# Xmega.net
KiCad netlist of a schematic drawn in Altium Designer
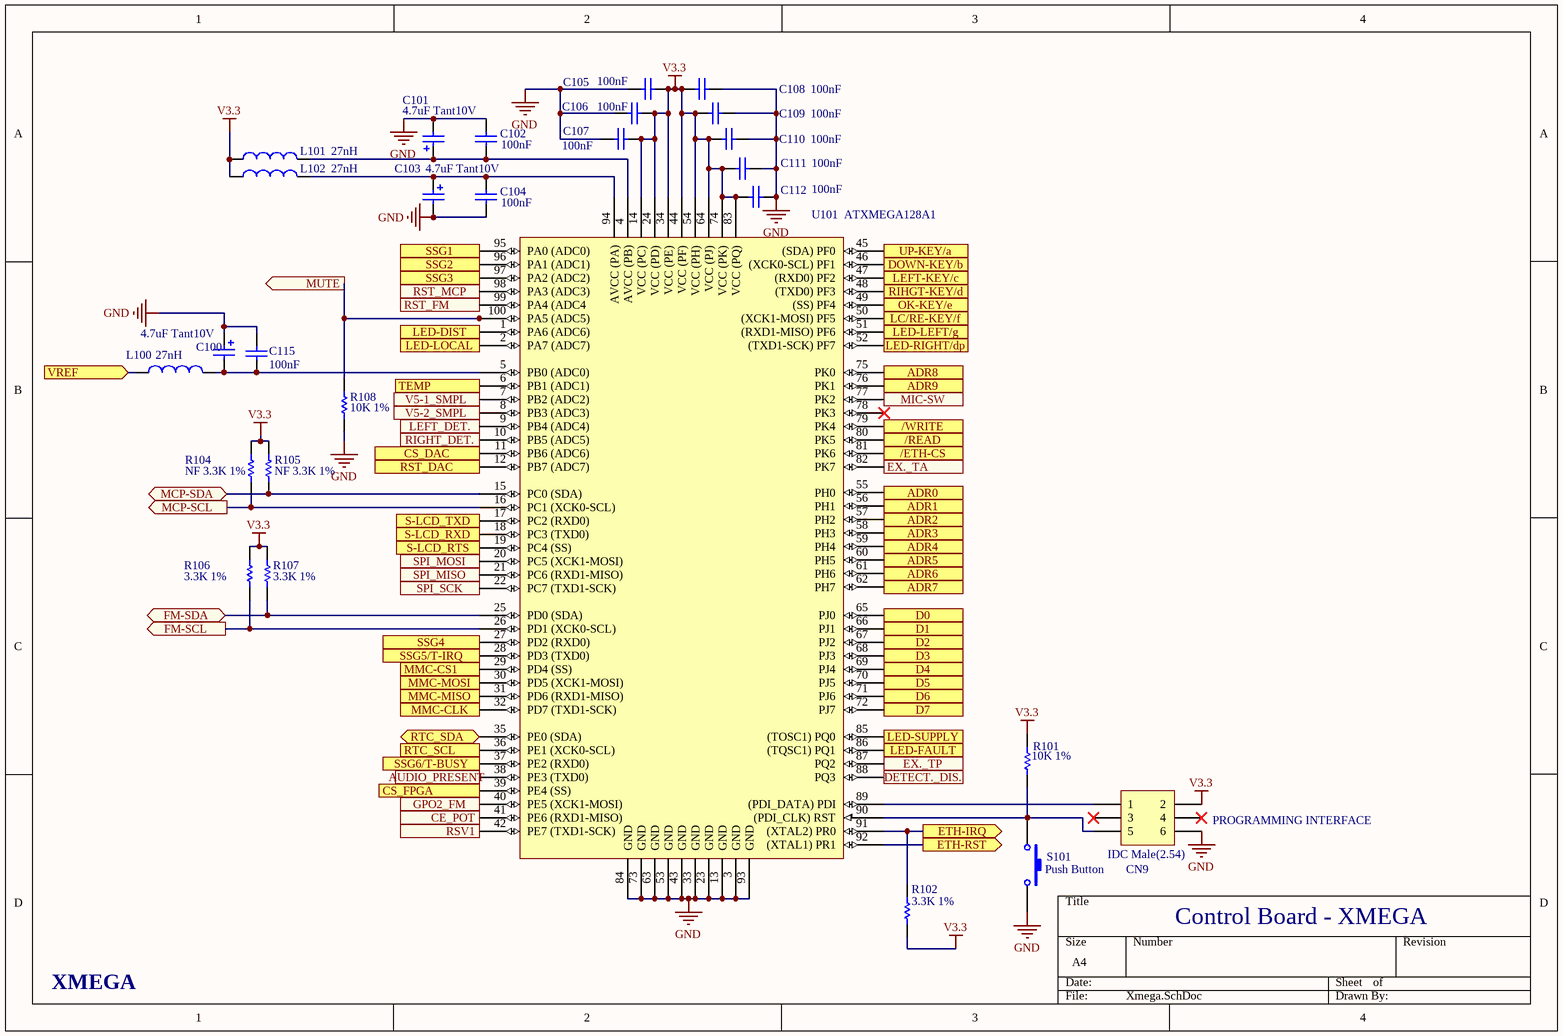
[diagram p0: Xmega.SchDoc]

(export (version "E")
  (design (tool "Eeschema 10.0.6"))
  (components
    (comp (ref "C100")
      (value "4.7uF Tant10V")
      (footprint "CAP-TAN")
      (description "Polarized Capacitor (Surface Mount)")
      (fields (field (name "PUBLISHER") "Altium Limited"))
      (libsource (lib "Miscellaneous Devices") (part "Cap Pol3"))
    )
    (comp (ref "C101")
      (value "4.7uF Tant10V")
      (footprint "A")
      (description "Polarized Capacitor (Surface Mount)")
      (fields (field (name "PUBLISHER") "Altium Limited"))
      (libsource (lib "Miscellaneous Devices") (part "Cap Pol3"))
    )
    (comp (ref "C102")
      (value "100nF")
      (footprint "1206_FA")
      (description "Capacitor (Semiconductor SIM Model)")
      (fields (field (name "PUBLISHER") "Altium Limited"))
      (libsource (lib "Miscellaneous Devices") (part "Cap Semi"))
    )
    (comp (ref "C103")
      (value "4.7uF Tant10V")
      (footprint "A")
      (description "Polarized Capacitor (Surface Mount)")
      (fields (field (name "PUBLISHER") "Altium Limited"))
      (libsource (lib "Miscellaneous Devices") (part "Cap Pol3"))
    )
    (comp (ref "C104")
      (value "100nF")
      (footprint "1206_FA")
      (description "Capacitor (Semiconductor SIM Model)")
      (fields (field (name "PUBLISHER") "Altium Limited"))
      (libsource (lib "Miscellaneous Devices") (part "Cap Semi"))
    )
    (comp (ref "C105")
      (value "100nF")
      (footprint "1206_FA")
      (description "Capacitor (Semiconductor SIM Model)")
      (fields (field (name "PUBLISHER") "Altium Limited"))
      (libsource (lib "Miscellaneous Devices") (part "Cap Semi"))
    )
    (comp (ref "C106")
      (value "100nF")
      (footprint "1206_FA")
      (description "Capacitor (Semiconductor SIM Model)")
      (fields (field (name "PUBLISHER") "Altium Limited"))
      (libsource (lib "Miscellaneous Devices") (part "Cap Semi"))
    )
    (comp (ref "C107")
      (value "100nF")
      (footprint "1206_FA")
      (description "Capacitor (Semiconductor SIM Model)")
      (fields (field (name "PUBLISHER") "Altium Limited"))
      (libsource (lib "Miscellaneous Devices") (part "Cap Semi"))
    )
    (comp (ref "C108")
      (value "100nF")
      (footprint "1206_FA")
      (description "Capacitor (Semiconductor SIM Model)")
      (fields (field (name "PUBLISHER") "Altium Limited"))
      (libsource (lib "Miscellaneous Devices") (part "Cap Semi"))
    )
    (comp (ref "C109")
      (value "100nF")
      (footprint "1206_FA")
      (description "Capacitor (Semiconductor SIM Model)")
      (fields (field (name "PUBLISHER") "Altium Limited"))
      (libsource (lib "Miscellaneous Devices") (part "Cap Semi"))
    )
    (comp (ref "C110")
      (value "100nF")
      (footprint "1206_FA")
      (description "Capacitor (Semiconductor SIM Model)")
      (fields (field (name "PUBLISHER") "Altium Limited"))
      (libsource (lib "Miscellaneous Devices") (part "Cap Semi"))
    )
    (comp (ref "C111")
      (value "100nF")
      (footprint "1206_FA")
      (description "Capacitor (Semiconductor SIM Model)")
      (fields (field (name "PUBLISHER") "Altium Limited"))
      (libsource (lib "Miscellaneous Devices") (part "Cap Semi"))
    )
    (comp (ref "C112")
      (value "100nF")
      (footprint "1206_FA")
      (description "Capacitor (Semiconductor SIM Model)")
      (fields (field (name "PUBLISHER") "Altium Limited"))
      (libsource (lib "Miscellaneous Devices") (part "Cap Semi"))
    )
    (comp (ref "C115")
      (value "100nF")
      (footprint "0805_FA")
      (description "Capacitor (Semiconductor SIM Model)")
      (fields (field (name "PUBLISHER") "Altium Limited"))
      (libsource (lib "Miscellaneous Devices") (part "Cap Semi"))
    )
    (comp (ref "CN9")
      (value "IDC Male(2.54)")
      (footprint "HDR2X3_M")
      (description "Header 3x2")
      (fields (field (name "PUBLISHER") "Altium Limited"))
      (libsource (lib "Miscellaneous Connectors") (part "Header 3X2"))
    )
    (comp (ref "L100")
      (value "27nH")
      (footprint "1210_FA")
      (description "Inductor")
      (fields (field (name "PUBLISHER") "Altium Limited"))
      (libsource (lib "Miscellaneous Devices") (part "Inductor"))
    )
    (comp (ref "L101")
      (value "27nH")
      (footprint "1210_FA")
      (description "Inductor")
      (fields (field (name "PUBLISHER") "Altium Limited"))
      (libsource (lib "Miscellaneous Devices") (part "Inductor"))
    )
    (comp (ref "L102")
      (value "27nH")
      (footprint "1210_FA")
      (description "Inductor")
      (fields (field (name "PUBLISHER") "Altium Limited"))
      (libsource (lib "Miscellaneous Devices") (part "Inductor"))
    )
    (comp (ref "R101")
      (value "10K 1%")
      (footprint "1206_FA")
      (description "Semiconductor Resistor")
      (fields (field (name "PUBLISHER") "Altium Limited"))
      (libsource (lib "Miscellaneous Devices") (part "Res Semi"))
    )
    (comp (ref "R102")
      (value "3.3K 1%")
      (footprint "1206_FA")
      (description "Semiconductor Resistor")
      (fields (field (name "PUBLISHER") "Altium Limited"))
      (libsource (lib "Miscellaneous Devices") (part "Res Semi"))
    )
    (comp (ref "R104")
      (value "NF 3.3K 1%")
      (footprint "1206_FA")
      (description "Semiconductor Resistor")
      (fields (field (name "PUBLISHER") "Altium Limited"))
      (libsource (lib "Miscellaneous Devices") (part "Res Semi"))
    )
    (comp (ref "R105")
      (value "NF 3.3K 1%")
      (footprint "1206_FA")
      (description "Semiconductor Resistor")
      (fields (field (name "PUBLISHER") "Altium Limited"))
      (libsource (lib "Miscellaneous Devices") (part "Res Semi"))
    )
    (comp (ref "R106")
      (value "3.3K 1%")
      (footprint "1206_FA")
      (description "Semiconductor Resistor")
      (fields (field (name "PUBLISHER") "Altium Limited"))
      (libsource (lib "Miscellaneous Devices") (part "Res Semi"))
    )
    (comp (ref "R107")
      (value "3.3K 1%")
      (footprint "1206_FA")
      (description "Semiconductor Resistor")
      (fields (field (name "PUBLISHER") "Altium Limited"))
      (libsource (lib "Miscellaneous Devices") (part "Res Semi"))
    )
    (comp (ref "R108")
      (value "10K 1%")
      (footprint "1206_FA")
      (description "Semiconductor Resistor")
      (fields (field (name "PUBLISHER") "Altium Limited"))
      (libsource (lib "Miscellaneous Devices") (part "Res Semi"))
    )
    (comp (ref "S101")
      (value "Push Button")
      (footprint "SPS2_M(2Pin)")
      (description "Switch")
      (fields (field (name "PUBLISHER") "Altium Limited"))
      (libsource (lib "Miscellaneous Devices") (part "SW-PB"))
    )
    (comp (ref "U101")
      (value "ATXMEGA128A1")
      (footprint "100T1_N")
      (description "Atmel Microcontroller - Library created by carel..  <www.mpfreezone.com>")
      (libsource (lib "Xmega") (part "ATMEGA163_DIP40"))
    )
  )
  (nets
    (net (code "1") (name "/ADR0") (class "Default")
      (node (ref "U101") (pin "55") (pinfunction "PH0_55") (pintype "bidirectional"))
    )
    (net (code "2") (name "/ADR1") (class "Default")
      (node (ref "U101") (pin "56") (pinfunction "PH1_56") (pintype "bidirectional"))
    )
    (net (code "3") (name "/ADR2") (class "Default")
      (node (ref "U101") (pin "57") (pinfunction "PH2_57") (pintype "bidirectional"))
    )
    (net (code "4") (name "/ADR3") (class "Default")
      (node (ref "U101") (pin "58") (pinfunction "PH3_58") (pintype "bidirectional"))
    )
    (net (code "5") (name "/ADR4") (class "Default")
      (node (ref "U101") (pin "59") (pinfunction "PH4_59") (pintype "bidirectional"))
    )
    (net (code "6") (name "/ADR5") (class "Default")
      (node (ref "U101") (pin "60") (pinfunction "PH5_60") (pintype "bidirectional"))
    )
    (net (code "7") (name "/ADR6") (class "Default")
      (node (ref "U101") (pin "61") (pinfunction "PH6_61") (pintype "bidirectional"))
    )
    (net (code "8") (name "/ADR7") (class "Default")
      (node (ref "U101") (pin "62") (pinfunction "PH7_62") (pintype "bidirectional"))
    )
    (net (code "9") (name "/ADR8") (class "Default")
      (node (ref "U101") (pin "75") (pinfunction "PK0_75") (pintype "bidirectional"))
    )
    (net (code "10") (name "/ADR9") (class "Default")
      (node (ref "U101") (pin "76") (pinfunction "PK1_76") (pintype "bidirectional"))
    )
    (net (code "11") (name "/AUDIO_PRESENT") (class "Default")
      (node (ref "U101") (pin "38") (pinfunction "PE3_(TXD0)_38") (pintype "bidirectional"))
    )
    (net (code "12") (name "/CE_POT") (class "Default")
      (node (ref "U101") (pin "41") (pinfunction "PE6_(RXD1-MISO)_41") (pintype "bidirectional"))
    )
    (net (code "13") (name "/CS_DAC") (class "Default")
      (node (ref "U101") (pin "11") (pinfunction "PB6_(ADC6)_11") (pintype "bidirectional"))
    )
    (net (code "14") (name "/CS_FPGA") (class "Default")
      (node (ref "U101") (pin "39") (pinfunction "PE4_(SS)_39") (pintype "bidirectional"))
    )
    (net (code "15") (name "/D0") (class "Default")
      (node (ref "U101") (pin "65") (pinfunction "PJ0_65") (pintype "bidirectional"))
    )
    (net (code "16") (name "/D1") (class "Default")
      (node (ref "U101") (pin "66") (pinfunction "PJ1_66") (pintype "bidirectional"))
    )
    (net (code "17") (name "/D2") (class "Default")
      (node (ref "U101") (pin "67") (pinfunction "PJ2_67") (pintype "bidirectional"))
    )
    (net (code "18") (name "/D3") (class "Default")
      (node (ref "U101") (pin "68") (pinfunction "PJ3_68") (pintype "bidirectional"))
    )
    (net (code "19") (name "/D4") (class "Default")
      (node (ref "U101") (pin "69") (pinfunction "PJ4_69") (pintype "bidirectional"))
    )
    (net (code "20") (name "/D5") (class "Default")
      (node (ref "U101") (pin "70") (pinfunction "PJ5_70") (pintype "bidirectional"))
    )
    (net (code "21") (name "/D6") (class "Default")
      (node (ref "U101") (pin "71") (pinfunction "PJ6_71") (pintype "bidirectional"))
    )
    (net (code "22") (name "/D7") (class "Default")
      (node (ref "U101") (pin "72") (pinfunction "PJ7_72") (pintype "bidirectional"))
    )
    (net (code "23") (name "/DETECT._DIS.") (class "Default")
      (node (ref "U101") (pin "88") (pinfunction "PQ3_88") (pintype "bidirectional"))
    )
    (net (code "24") (name "/DOWN-KEY{slash}b") (class "Default")
      (node (ref "U101") (pin "46") (pinfunction "(XCK0-SCL)_PF1_46") (pintype "bidirectional"))
    )
    (net (code "25") (name "/ETH-IRQ") (class "Default")
      (node (ref "R102") (pin "2") (pinfunction "2_2") (pintype "passive"))
      (node (ref "U101") (pin "91") (pinfunction "(XTAL2)_PR0_91") (pintype "bidirectional"))
    )
    (net (code "26") (name "/ETH-RST") (class "Default")
      (node (ref "U101") (pin "92") (pinfunction "(XTAL1)_PR1_92") (pintype "bidirectional"))
    )
    (net (code "27") (name "/EX._TA") (class "Default")
      (node (ref "U101") (pin "82") (pinfunction "PK7_82") (pintype "bidirectional"))
    )
    (net (code "28") (name "/EX._TP") (class "Default")
      (node (ref "U101") (pin "87") (pinfunction "PQ2_87") (pintype "bidirectional"))
    )
    (net (code "29") (name "/FM-SCL") (class "Default")
      (node (ref "R106") (pin "1") (pinfunction "1_1") (pintype "passive"))
      (node (ref "U101") (pin "26") (pinfunction "PD1_(XCK0-SCL)_26") (pintype "bidirectional"))
    )
    (net (code "30") (name "/FM-SDA") (class "Default")
      (node (ref "R107") (pin "1") (pinfunction "1_1") (pintype "passive"))
      (node (ref "U101") (pin "25") (pinfunction "PD0_(SDA)_25") (pintype "bidirectional"))
    )
    (net (code "31") (name "/GPO2_FM") (class "Default")
      (node (ref "U101") (pin "40") (pinfunction "PE5_(XCK1-MOSI)_40") (pintype "bidirectional"))
    )
    (net (code "32") (name "/LC{slash}RE-KEY{slash}f") (class "Default")
      (node (ref "U101") (pin "50") (pinfunction "(XCK1-MOSI)_PF5_50") (pintype "bidirectional"))
    )
    (net (code "33") (name "/LED-DIST") (class "Default")
      (node (ref "U101") (pin "1") (pinfunction "PA6_(ADC6)_1") (pintype "bidirectional"))
    )
    (net (code "34") (name "/LED-FAULT") (class "Default")
      (node (ref "U101") (pin "86") (pinfunction "(TQSC1)_PQ1_86") (pintype "bidirectional"))
    )
    (net (code "35") (name "/LED-LEFT{slash}g") (class "Default")
      (node (ref "U101") (pin "51") (pinfunction "(RXD1-MISO)_PF6_51") (pintype "bidirectional"))
    )
    (net (code "36") (name "/LED-LOCAL") (class "Default")
      (node (ref "U101") (pin "2") (pinfunction "PA7_(ADC7)_2") (pintype "bidirectional"))
    )
    (net (code "37") (name "/LED-RIGHT{slash}dp") (class "Default")
      (node (ref "U101") (pin "52") (pinfunction "(TXD1-SCK)_PF7_52") (pintype "bidirectional"))
    )
    (net (code "38") (name "/LED-SUPPLY") (class "Default")
      (node (ref "U101") (pin "85") (pinfunction "(TOSC1)_PQ0_85") (pintype "bidirectional"))
    )
    (net (code "39") (name "/LEFT-KEY{slash}c") (class "Default")
      (node (ref "U101") (pin "47") (pinfunction "(RXD0)_PF2_47") (pintype "bidirectional"))
    )
    (net (code "40") (name "/LEFT_DET.") (class "Default")
      (node (ref "U101") (pin "9") (pinfunction "PB4_(ADC4)_9") (pintype "bidirectional"))
    )
    (net (code "41") (name "/MCP-SCL") (class "Default")
      (node (ref "R104") (pin "1") (pinfunction "1_1") (pintype "passive"))
      (node (ref "U101") (pin "16") (pinfunction "PC1_(XCK0-SCL)_16") (pintype "bidirectional"))
    )
    (net (code "42") (name "/MCP-SDA") (class "Default")
      (node (ref "R105") (pin "1") (pinfunction "1_1") (pintype "passive"))
      (node (ref "U101") (pin "15") (pinfunction "PC0_(SDA)_15") (pintype "bidirectional"))
    )
    (net (code "43") (name "/MIC-SW") (class "Default")
      (node (ref "U101") (pin "77") (pinfunction "PK2_77") (pintype "bidirectional"))
    )
    (net (code "44") (name "/MMC-CLK") (class "Default")
      (node (ref "U101") (pin "32") (pinfunction "PD7_(TXD1-SCK)_32") (pintype "bidirectional"))
    )
    (net (code "45") (name "/MMC-CS1") (class "Default")
      (node (ref "U101") (pin "29") (pinfunction "PD4_(SS)_29") (pintype "bidirectional"))
    )
    (net (code "46") (name "/MMC-MISO") (class "Default")
      (node (ref "U101") (pin "31") (pinfunction "PD6_(RXD1-MISO)_31") (pintype "bidirectional"))
    )
    (net (code "47") (name "/MMC-MOSI") (class "Default")
      (node (ref "U101") (pin "30") (pinfunction "PD5_(XCK1-MOSI)_30") (pintype "bidirectional"))
    )
    (net (code "48") (name "/MUTE") (class "Default")
      (node (ref "R108") (pin "2") (pinfunction "2_2") (pintype "passive"))
      (node (ref "U101") (pin "100") (pinfunction "PA5_(ADC5)_100") (pintype "bidirectional"))
    )
    (net (code "49") (name "/OK-KEY{slash}e") (class "Default")
      (node (ref "U101") (pin "49") (pinfunction "(SS)_PF4_49") (pintype "bidirectional"))
    )
    (net (code "50") (name "/RIGHT_DET.") (class "Default")
      (node (ref "U101") (pin "10") (pinfunction "PB5_(ADC5)_10") (pintype "bidirectional"))
    )
    (net (code "51") (name "/RIHGT-KEY{slash}d") (class "Default")
      (node (ref "U101") (pin "48") (pinfunction "(TXD0)_PF3_48") (pintype "bidirectional"))
    )
    (net (code "52") (name "/RST_DAC") (class "Default")
      (node (ref "U101") (pin "12") (pinfunction "PB7_(ADC7)_12") (pintype "bidirectional"))
    )
    (net (code "53") (name "/RST_FM") (class "Default")
      (node (ref "U101") (pin "99") (pinfunction "PA4_(ADC4_99") (pintype "bidirectional"))
    )
    (net (code "54") (name "/RST_MCP") (class "Default")
      (node (ref "U101") (pin "98") (pinfunction "PA3_(ADC3)_98") (pintype "bidirectional"))
    )
    (net (code "55") (name "/RSV1") (class "Default")
      (node (ref "U101") (pin "42") (pinfunction "PE7_(TXD1-SCK)_42") (pintype "bidirectional"))
    )
    (net (code "56") (name "/RTC_SCL") (class "Default")
      (node (ref "U101") (pin "36") (pinfunction "PE1_(XCK0-SCL)_36") (pintype "bidirectional"))
    )
    (net (code "57") (name "/RTC_SDA") (class "Default")
      (node (ref "U101") (pin "35") (pinfunction "PE0_(SDA)_35") (pintype "bidirectional"))
    )
    (net (code "58") (name "/S-LCD_RTS") (class "Default")
      (node (ref "U101") (pin "19") (pinfunction "PC4_(SS)_19") (pintype "bidirectional"))
    )
    (net (code "59") (name "/S-LCD_RXD") (class "Default")
      (node (ref "U101") (pin "18") (pinfunction "PC3_(TXD0)_18") (pintype "bidirectional"))
    )
    (net (code "60") (name "/S-LCD_TXD") (class "Default")
      (node (ref "U101") (pin "17") (pinfunction "PC2_(RXD0)_17") (pintype "bidirectional"))
    )
    (net (code "61") (name "/SPI_MISO") (class "Default")
      (node (ref "U101") (pin "21") (pinfunction "PC6_(RXD1-MISO)_21") (pintype "bidirectional"))
    )
    (net (code "62") (name "/SPI_MOSI") (class "Default")
      (node (ref "U101") (pin "20") (pinfunction "PC5_(XCK1-MOSI)_20") (pintype "bidirectional"))
    )
    (net (code "63") (name "/SPI_SCK") (class "Default")
      (node (ref "U101") (pin "22") (pinfunction "PC7_(TXD1-SCK)_22") (pintype "bidirectional"))
    )
    (net (code "64") (name "/SSG1") (class "Default")
      (node (ref "U101") (pin "95") (pinfunction "PA0_(ADC0)_95") (pintype "bidirectional"))
    )
    (net (code "65") (name "/SSG2") (class "Default")
      (node (ref "U101") (pin "96") (pinfunction "PA1_(ADC1)_96") (pintype "bidirectional"))
    )
    (net (code "66") (name "/SSG3") (class "Default")
      (node (ref "U101") (pin "97") (pinfunction "PA2_(ADC2)_97") (pintype "bidirectional"))
    )
    (net (code "67") (name "/SSG4") (class "Default")
      (node (ref "U101") (pin "27") (pinfunction "PD2_(RXD0)_27") (pintype "bidirectional"))
    )
    (net (code "68") (name "/SSG5{slash}T-IRQ") (class "Default")
      (node (ref "U101") (pin "28") (pinfunction "PD3_(TXD0)_28") (pintype "bidirectional"))
    )
    (net (code "69") (name "/SSG6{slash}T-BUSY") (class "Default")
      (node (ref "U101") (pin "37") (pinfunction "PE2_(RXD0)_37") (pintype "bidirectional"))
    )
    (net (code "70") (name "/TEMP") (class "Default")
      (node (ref "U101") (pin "6") (pinfunction "PB1_(ADC1)_6") (pintype "bidirectional"))
    )
    (net (code "71") (name "/UP-KEY{slash}a") (class "Default")
      (node (ref "U101") (pin "45") (pinfunction "(SDA)_PF0_45") (pintype "bidirectional"))
    )
    (net (code "72") (name "/V5-1_SMPL") (class "Default")
      (node (ref "U101") (pin "7") (pinfunction "PB2_(ADC2)_7") (pintype "bidirectional"))
    )
    (net (code "73") (name "/V5-2_SMPL") (class "Default")
      (node (ref "U101") (pin "8") (pinfunction "PB3_(ADC3)_8") (pintype "bidirectional"))
    )
    (net (code "74") (name "/VREF") (class "Default")
      (node (ref "L100") (pin "1") (pinfunction "1_1") (pintype "passive"))
    )
    (net (code "75") (name "/{slash}ETH-CS") (class "Default")
      (node (ref "U101") (pin "81") (pinfunction "PK6_81") (pintype "bidirectional"))
    )
    (net (code "76") (name "/{slash}READ") (class "Default")
      (node (ref "U101") (pin "80") (pinfunction "PK5_80") (pintype "bidirectional"))
    )
    (net (code "77") (name "/{slash}WRITE") (class "Default")
      (node (ref "U101") (pin "79") (pinfunction "PK4_79") (pintype "bidirectional"))
    )
    (net (code "78") (name "GND") (class "Default")
      (node (ref "C100") (pin "1") (pinfunction "1_1") (pintype "passive"))
      (node (ref "C101") (pin "2") (pinfunction "2_2") (pintype "passive"))
      (node (ref "C102") (pin "2") (pinfunction "2_2") (pintype "passive"))
      (node (ref "C103") (pin "2") (pinfunction "2_2") (pintype "passive"))
      (node (ref "C104") (pin "1") (pinfunction "1_1") (pintype "passive"))
      (node (ref "C105") (pin "2") (pinfunction "2_2") (pintype "passive"))
      (node (ref "C106") (pin "2") (pinfunction "2_2") (pintype "passive"))
      (node (ref "C107") (pin "2") (pinfunction "2_2") (pintype "passive"))
      (node (ref "C108") (pin "1") (pinfunction "1_1") (pintype "passive"))
      (node (ref "C109") (pin "1") (pinfunction "1_1") (pintype "passive"))
      (node (ref "C110") (pin "1") (pinfunction "1_1") (pintype "passive"))
      (node (ref "C111") (pin "1") (pinfunction "1_1") (pintype "passive"))
      (node (ref "C112") (pin "1") (pinfunction "1_1") (pintype "passive"))
      (node (ref "C115") (pin "2") (pinfunction "2_2") (pintype "passive"))
      (node (ref "CN9") (pin "6") (pinfunction "6_6") (pintype "passive"))
      (node (ref "R108") (pin "1") (pinfunction "1_1") (pintype "passive"))
      (node (ref "S101") (pin "2") (pinfunction "2_2") (pintype "passive"))
      (node (ref "U101") (pin "13") (pinfunction "GND_13") (pintype "power_in"))
      (node (ref "U101") (pin "23") (pinfunction "GND_23") (pintype "power_in"))
      (node (ref "U101") (pin "3") (pinfunction "GND_3") (pintype "power_in"))
      (node (ref "U101") (pin "33") (pinfunction "GND_33") (pintype "power_in"))
      (node (ref "U101") (pin "43") (pinfunction "GND_43") (pintype "power_in"))
      (node (ref "U101") (pin "53") (pinfunction "GND_53") (pintype "power_in"))
      (node (ref "U101") (pin "63") (pinfunction "GND_63") (pintype "power_in"))
      (node (ref "U101") (pin "73") (pinfunction "GND_73") (pintype "power_in"))
      (node (ref "U101") (pin "84") (pinfunction "GND_84") (pintype "power_in"))
      (node (ref "U101") (pin "93") (pinfunction "GND_93") (pintype "power_in"))
    )
    (net (code "79") (name "Net-(U101-(PDI_CLK)_RST)") (class "Default")
      (node (ref "CN9") (pin "5") (pinfunction "5_5") (pintype "passive"))
      (node (ref "R101") (pin "1") (pinfunction "1_1") (pintype "passive"))
      (node (ref "S101") (pin "1") (pinfunction "1_1") (pintype "passive"))
      (node (ref "U101") (pin "90") (pinfunction "(PDI_CLK)_RST_90") (pintype "input"))
    )
    (net (code "80") (name "Net-(U101-(PDI_DATA)_PDI)") (class "Default")
      (node (ref "CN9") (pin "1") (pinfunction "1_1") (pintype "passive"))
      (node (ref "U101") (pin "89") (pinfunction "(PDI_DATA)_PDI_89") (pintype "bidirectional"))
    )
    (net (code "81") (name "Net-(U101-AVCC_(PA))") (class "Default")
      (node (ref "C103") (pin "1") (pinfunction "1_1") (pintype "passive"))
      (node (ref "C104") (pin "2") (pinfunction "2_2") (pintype "passive"))
      (node (ref "L102") (pin "2") (pinfunction "2_2") (pintype "passive"))
      (node (ref "U101") (pin "94") (pinfunction "AVCC_(PA)_94") (pintype "power_in"))
    )
    (net (code "82") (name "Net-(U101-AVCC_(PB))") (class "Default")
      (node (ref "C101") (pin "1") (pinfunction "1_1") (pintype "passive"))
      (node (ref "C102") (pin "1") (pinfunction "1_1") (pintype "passive"))
      (node (ref "L101") (pin "2") (pinfunction "2_2") (pintype "passive"))
      (node (ref "U101") (pin "4") (pinfunction "AVCC_(PB)_4") (pintype "power_in"))
    )
    (net (code "83") (name "Net-(U101-PB0_(ADC0))") (class "Default")
      (node (ref "C100") (pin "2") (pinfunction "2_2") (pintype "passive"))
      (node (ref "C115") (pin "1") (pinfunction "1_1") (pintype "passive"))
      (node (ref "L100") (pin "2") (pinfunction "2_2") (pintype "passive"))
      (node (ref "U101") (pin "5") (pinfunction "PB0_(ADC0)_5") (pintype "bidirectional"))
    )
    (net (code "84") (name "V3.3") (class "Default")
      (node (ref "C105") (pin "1") (pinfunction "1_1") (pintype "passive"))
      (node (ref "C106") (pin "1") (pinfunction "1_1") (pintype "passive"))
      (node (ref "C107") (pin "1") (pinfunction "1_1") (pintype "passive"))
      (node (ref "C108") (pin "2") (pinfunction "2_2") (pintype "passive"))
      (node (ref "C109") (pin "2") (pinfunction "2_2") (pintype "passive"))
      (node (ref "C110") (pin "2") (pinfunction "2_2") (pintype "passive"))
      (node (ref "C111") (pin "2") (pinfunction "2_2") (pintype "passive"))
      (node (ref "C112") (pin "2") (pinfunction "2_2") (pintype "passive"))
      (node (ref "CN9") (pin "2") (pinfunction "2_2") (pintype "passive"))
      (node (ref "L101") (pin "1") (pinfunction "1_1") (pintype "passive"))
      (node (ref "L102") (pin "1") (pinfunction "1_1") (pintype "passive"))
      (node (ref "R101") (pin "2") (pinfunction "2_2") (pintype "passive"))
      (node (ref "R102") (pin "1") (pinfunction "1_1") (pintype "passive"))
      (node (ref "R104") (pin "2") (pinfunction "2_2") (pintype "passive"))
      (node (ref "R105") (pin "2") (pinfunction "2_2") (pintype "passive"))
      (node (ref "R106") (pin "2") (pinfunction "2_2") (pintype "passive"))
      (node (ref "R107") (pin "2") (pinfunction "2_2") (pintype "passive"))
      (node (ref "U101") (pin "14") (pinfunction "VCC_(PC)_14") (pintype "power_in"))
      (node (ref "U101") (pin "24") (pinfunction "VCC_(PD)_24") (pintype "power_in"))
      (node (ref "U101") (pin "34") (pinfunction "VCC_(PE)_34") (pintype "power_in"))
      (node (ref "U101") (pin "44") (pinfunction "VCC_(PF)_44") (pintype "power_in"))
      (node (ref "U101") (pin "54") (pinfunction "VCC_(PH)_54") (pintype "power_in"))
      (node (ref "U101") (pin "64") (pinfunction "VCC_(PJ)_64") (pintype "power_in"))
      (node (ref "U101") (pin "74") (pinfunction "VCC_(PK)_74") (pintype "power_in"))
      (node (ref "U101") (pin "83") (pinfunction "VCC_(PQ)_83") (pintype "power_in"))
    )
    (net (code "85") (name "unconnected-(CN9-Pad3)") (class "Default")
      (node (ref "CN9") (pin "3") (pinfunction "3_3") (pintype "passive+no_connect"))
    )
    (net (code "86") (name "unconnected-(CN9-Pad4)") (class "Default")
      (node (ref "CN9") (pin "4") (pinfunction "4_4") (pintype "passive+no_connect"))
    )
    (net (code "87") (name "unconnected-(U101-PK3-Pad78)") (class "Default")
      (node (ref "U101") (pin "78") (pinfunction "PK3_78") (pintype "bidirectional+no_connect"))
    )
  )
)
